# node_shield.net
KiCad netlist of a schematic drawn in EAGLE
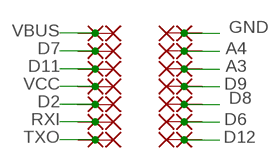
[diagram p0: schematic, sheet 1]

(export (version "E")
  (design (tool "Eeschema 10.0.6"))
  (components
    (comp (ref "PAD1")
      (value "SMD2")
      (footprint "eagle-import:SMD1,27-2,54")
      (libsource (lib "eagle-import") (part "SMD2"))
    )
    (comp (ref "PAD2")
      (value "SMD2")
      (footprint "eagle-import:SMD1,27-2,54")
      (libsource (lib "eagle-import") (part "SMD2"))
    )
    (comp (ref "PAD3")
      (value "SMD2")
      (footprint "eagle-import:SMD1,27-2,54")
      (libsource (lib "eagle-import") (part "SMD2"))
    )
    (comp (ref "PAD4")
      (value "SMD2")
      (footprint "eagle-import:SMD1,27-2,54")
      (libsource (lib "eagle-import") (part "SMD2"))
    )
    (comp (ref "PAD5")
      (value "SMD2")
      (footprint "eagle-import:SMD1,27-2,54")
      (libsource (lib "eagle-import") (part "SMD2"))
    )
    (comp (ref "PAD6")
      (value "SMD2")
      (footprint "eagle-import:SMD1,27-2,54")
      (libsource (lib "eagle-import") (part "SMD2"))
    )
    (comp (ref "PAD7")
      (value "SMD2")
      (footprint "eagle-import:SMD1,27-2,54")
      (libsource (lib "eagle-import") (part "SMD2"))
    )
    (comp (ref "PAD8")
      (value "SMD2")
      (footprint "eagle-import:SMD1,27-2,54")
      (libsource (lib "eagle-import") (part "SMD2"))
    )
    (comp (ref "PAD9")
      (value "SMD2")
      (footprint "eagle-import:SMD1,27-2,54")
      (libsource (lib "eagle-import") (part "SMD2"))
    )
    (comp (ref "PAD10")
      (value "SMD2")
      (footprint "eagle-import:SMD1,27-2,54")
      (libsource (lib "eagle-import") (part "SMD2"))
    )
    (comp (ref "PAD11")
      (value "SMD2")
      (footprint "eagle-import:SMD1,27-2,54")
      (libsource (lib "eagle-import") (part "SMD2"))
    )
    (comp (ref "PAD12")
      (value "SMD2")
      (footprint "eagle-import:SMD1,27-2,54")
      (libsource (lib "eagle-import") (part "SMD2"))
    )
    (comp (ref "PAD13")
      (value "SMD2")
      (footprint "eagle-import:SMD1,27-2,54")
      (libsource (lib "eagle-import") (part "SMD2"))
    )
    (comp (ref "PAD14")
      (value "SMD2")
      (footprint "eagle-import:SMD1,27-2,54")
      (libsource (lib "eagle-import") (part "SMD2"))
    )
    (comp (ref "PAD15")
      (value "SMD2")
      (footprint "eagle-import:SMD1,27-2,54")
      (libsource (lib "eagle-import") (part "SMD2"))
    )
    (comp (ref "PAD16")
      (value "SMD2")
      (footprint "eagle-import:SMD1,27-2,54")
      (libsource (lib "eagle-import") (part "SMD2"))
    )
    (comp (ref "PAD17")
      (value "SMD2")
      (footprint "eagle-import:SMD1,27-2,54")
      (libsource (lib "eagle-import") (part "SMD2"))
    )
    (comp (ref "PAD18")
      (value "SMD2")
      (footprint "eagle-import:SMD1,27-2,54")
      (libsource (lib "eagle-import") (part "SMD2"))
    )
    (comp (ref "PAD19")
      (value "SMD2")
      (footprint "eagle-import:SMD1,27-2,54")
      (libsource (lib "eagle-import") (part "SMD2"))
    )
    (comp (ref "PAD20")
      (value "SMD2")
      (footprint "eagle-import:SMD1,27-2,54")
      (libsource (lib "eagle-import") (part "SMD2"))
    )
    (comp (ref "PAD21")
      (value "SMD2")
      (footprint "eagle-import:SMD1,27-2,54")
      (libsource (lib "eagle-import") (part "SMD2"))
    )
    (comp (ref "PAD22")
      (value "SMD2")
      (footprint "eagle-import:SMD1,27-2,54")
      (libsource (lib "eagle-import") (part "SMD2"))
    )
    (comp (ref "PAD23")
      (value "SMD2")
      (footprint "eagle-import:SMD1,27-2,54")
      (libsource (lib "eagle-import") (part "SMD2"))
    )
    (comp (ref "PAD24")
      (value "SMD2")
      (footprint "eagle-import:SMD1,27-2,54")
      (libsource (lib "eagle-import") (part "SMD2"))
    )
    (comp (ref "PAD25")
      (value "SMD2")
      (footprint "eagle-import:SMD1,27-2,54")
      (libsource (lib "eagle-import") (part "SMD2"))
    )
    (comp (ref "PAD26")
      (value "SMD2")
      (footprint "eagle-import:SMD1,27-2,54")
      (libsource (lib "eagle-import") (part "SMD2"))
    )
    (comp (ref "PAD27")
      (value "SMD2")
      (footprint "eagle-import:SMD1,27-2,54")
      (libsource (lib "eagle-import") (part "SMD2"))
    )
    (comp (ref "PAD28")
      (value "SMD2")
      (footprint "eagle-import:SMD1,27-2,54")
      (libsource (lib "eagle-import") (part "SMD2"))
    )
  )
  (nets
    (net (code "1") (name "/A3") (class "Default")
      (node (ref "PAD24") (pin "1") (pinfunction "P_1") (pintype "passive"))
      (node (ref "PAD6") (pin "1") (pinfunction "P_1") (pintype "passive"))
    )
    (net (code "2") (name "/A4") (class "Default")
      (node (ref "PAD23") (pin "1") (pinfunction "P_1") (pintype "passive"))
      (node (ref "PAD5") (pin "1") (pinfunction "P_1") (pintype "passive"))
    )
    (net (code "3") (name "/D2") (class "Default")
      (node (ref "PAD12") (pin "1") (pinfunction "P_1") (pintype "passive"))
      (node (ref "PAD19") (pin "1") (pinfunction "P_1") (pintype "passive"))
    )
    (net (code "4") (name "/D6") (class "Default")
      (node (ref "PAD27") (pin "1") (pinfunction "P_1") (pintype "passive"))
      (node (ref "PAD4") (pin "1") (pinfunction "P_1") (pintype "passive"))
    )
    (net (code "5") (name "/D7") (class "Default")
      (node (ref "PAD16") (pin "1") (pinfunction "P_1") (pintype "passive"))
      (node (ref "PAD2") (pin "1") (pinfunction "P_1") (pintype "passive"))
    )
    (net (code "6") (name "/D8") (class "Default")
      (node (ref "PAD11") (pin "1") (pinfunction "P_1") (pintype "passive"))
      (node (ref "PAD26") (pin "1") (pinfunction "P_1") (pintype "passive"))
    )
    (net (code "7") (name "/D9") (class "Default")
      (node (ref "PAD1") (pin "1") (pinfunction "P_1") (pintype "passive"))
      (node (ref "PAD25") (pin "1") (pinfunction "P_1") (pintype "passive"))
    )
    (net (code "8") (name "/D11") (class "Default")
      (node (ref "PAD17") (pin "1") (pinfunction "P_1") (pintype "passive"))
      (node (ref "PAD7") (pin "1") (pinfunction "P_1") (pintype "passive"))
    )
    (net (code "9") (name "/D12") (class "Default")
      (node (ref "PAD28") (pin "1") (pinfunction "P_1") (pintype "passive"))
      (node (ref "PAD3") (pin "1") (pinfunction "P_1") (pintype "passive"))
    )
    (net (code "10") (name "/GND") (class "Default")
      (node (ref "PAD22") (pin "1") (pinfunction "P_1") (pintype "passive"))
      (node (ref "PAD8") (pin "1") (pinfunction "P_1") (pintype "passive"))
    )
    (net (code "11") (name "/RXI") (class "Default")
      (node (ref "PAD14") (pin "1") (pinfunction "P_1") (pintype "passive"))
      (node (ref "PAD20") (pin "1") (pinfunction "P_1") (pintype "passive"))
    )
    (net (code "12") (name "/TXO") (class "Default")
      (node (ref "PAD13") (pin "1") (pinfunction "P_1") (pintype "passive"))
      (node (ref "PAD21") (pin "1") (pinfunction "P_1") (pintype "passive"))
    )
    (net (code "13") (name "/VBUS") (class "Default")
      (node (ref "PAD15") (pin "1") (pinfunction "P_1") (pintype "passive"))
      (node (ref "PAD9") (pin "1") (pinfunction "P_1") (pintype "passive"))
    )
    (net (code "14") (name "/VCC") (class "Default")
      (node (ref "PAD10") (pin "1") (pinfunction "P_1") (pintype "passive"))
      (node (ref "PAD18") (pin "1") (pinfunction "P_1") (pintype "passive"))
    )
  )
)
